# 0129-codec-mp3.net
KiCad netlist of a schematic drawn in EAGLE
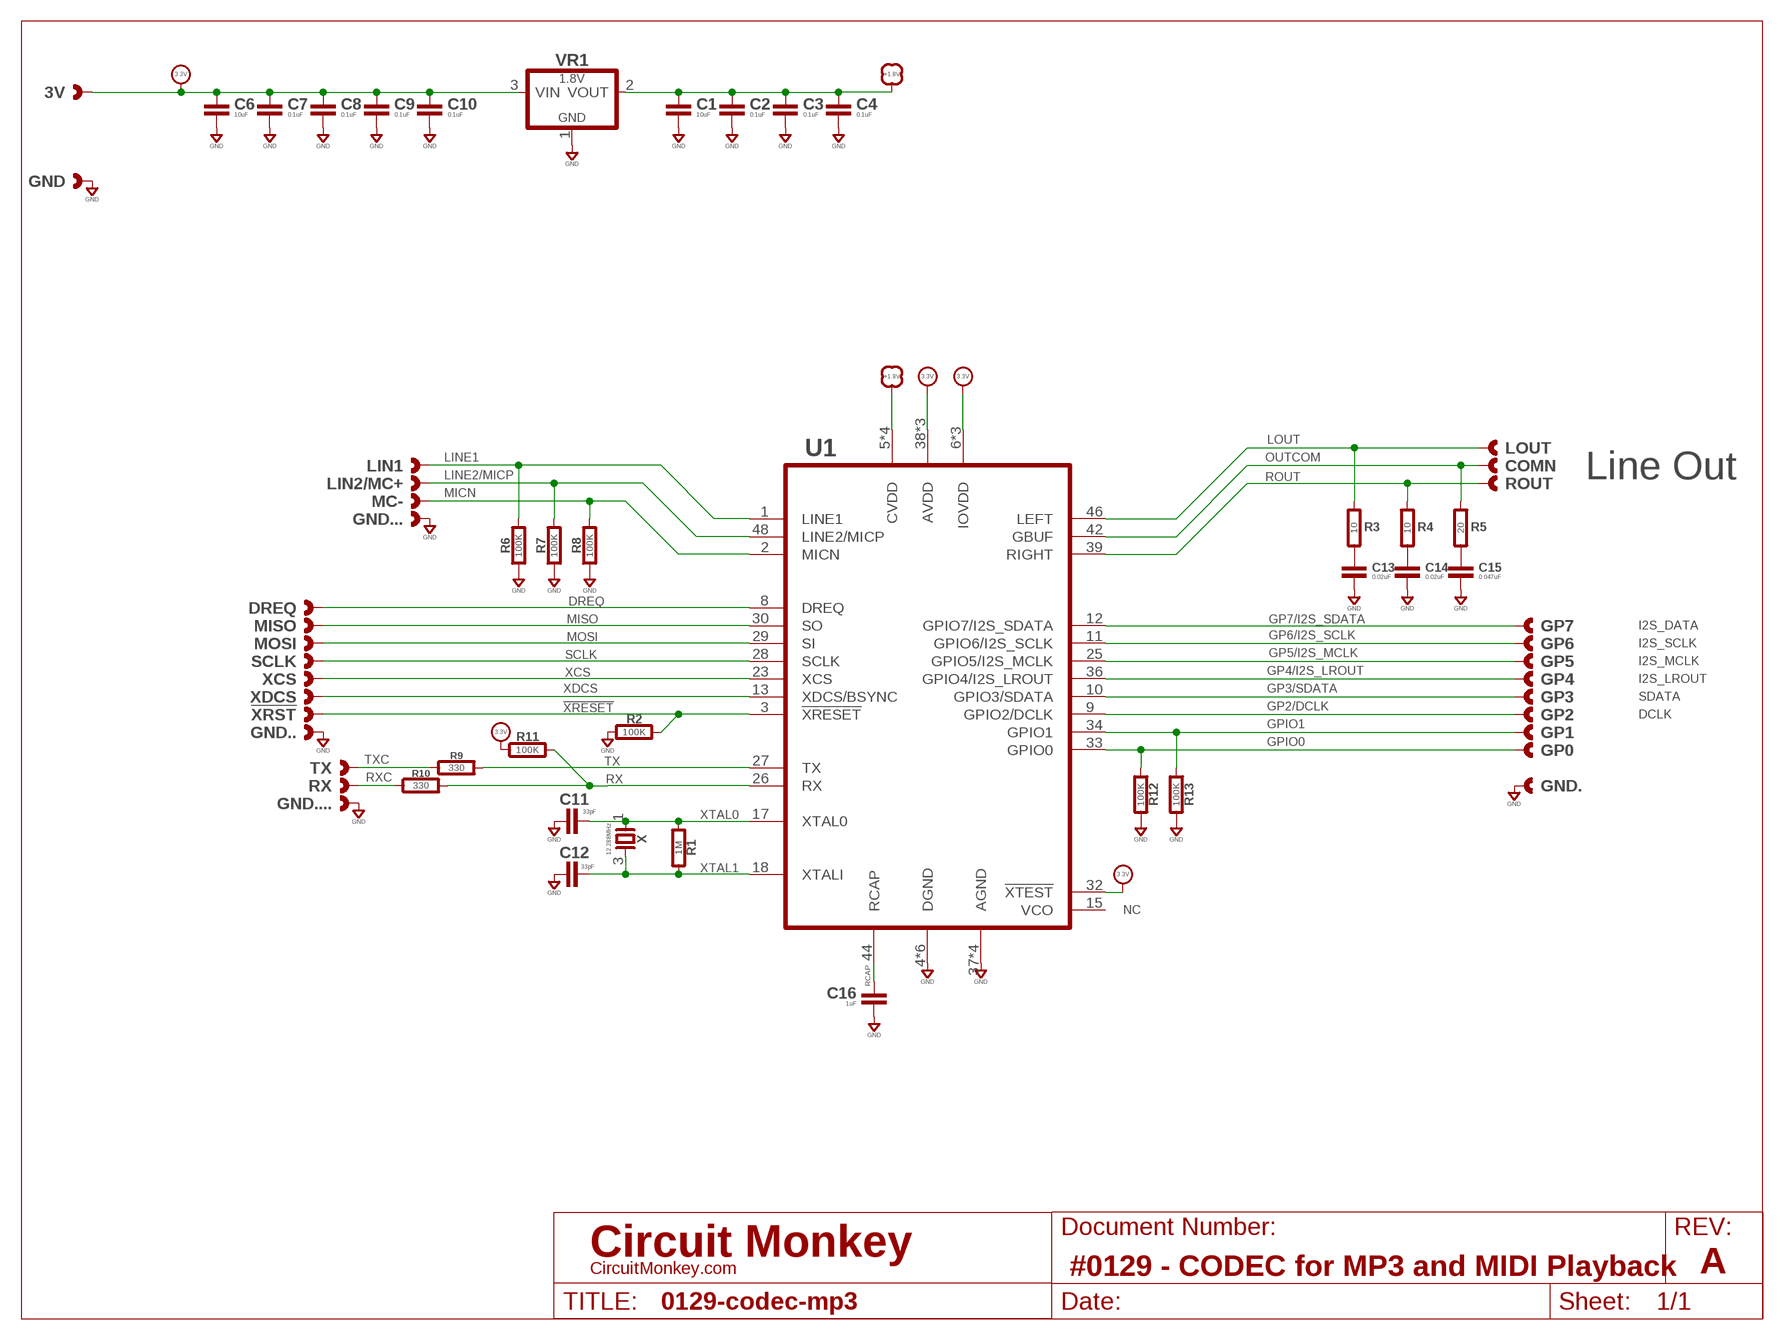
[diagram p0: schematic, sheet 1]

(export (version "E")
  (design (tool "Eeschema 10.0.6"))
  (components
    (comp (ref "!XRST")
      (value "CAST-01X12.00MM")
      (footprint "eagle-import:CAST01-2.00MM")
      (libsource (lib "eagle-import") (part "CAST-01X12.00MM"))
    )
    (comp (ref "3V")
      (value "CAST-01X12.00MM")
      (footprint "eagle-import:CAST01-2.00MM")
      (libsource (lib "eagle-import") (part "CAST-01X12.00MM"))
    )
    (comp (ref "C1")
      (value "10uF")
      (footprint "eagle-import:0603-CAP")
      (libsource (lib "eagle-import") (part "CAPACITOR0603"))
    )
    (comp (ref "C2")
      (value "0.1uF")
      (footprint "eagle-import:0603-CAP")
      (libsource (lib "eagle-import") (part "CAPACITOR0603"))
    )
    (comp (ref "C3")
      (value "0.1uF")
      (footprint "eagle-import:0603-CAP")
      (libsource (lib "eagle-import") (part "CAPACITOR0603"))
    )
    (comp (ref "C4")
      (value "0.1uF")
      (footprint "eagle-import:0603-CAP")
      (libsource (lib "eagle-import") (part "CAPACITOR0603"))
    )
    (comp (ref "C6")
      (value "10uF")
      (footprint "eagle-import:0603-CAP")
      (libsource (lib "eagle-import") (part "CAPACITOR0603"))
    )
    (comp (ref "C7")
      (value "0.1uF")
      (footprint "eagle-import:0603-CAP")
      (libsource (lib "eagle-import") (part "CAPACITOR0603"))
    )
    (comp (ref "C8")
      (value "0.1uF")
      (footprint "eagle-import:0603-CAP")
      (libsource (lib "eagle-import") (part "CAPACITOR0603"))
    )
    (comp (ref "C9")
      (value "0.1uF")
      (footprint "eagle-import:0603-CAP")
      (libsource (lib "eagle-import") (part "CAPACITOR0603"))
    )
    (comp (ref "C10")
      (value "0.1uF")
      (footprint "eagle-import:0603-CAP")
      (libsource (lib "eagle-import") (part "CAPACITOR0603"))
    )
    (comp (ref "C11")
      (value "33pF")
      (footprint "eagle-import:0603-CAP")
      (libsource (lib "eagle-import") (part "CAPACITOR0603"))
    )
    (comp (ref "C12")
      (value "33pF")
      (footprint "eagle-import:0603-CAP")
      (libsource (lib "eagle-import") (part "CAPACITOR0603"))
    )
    (comp (ref "C13")
      (value "0.02uF")
      (footprint "eagle-import:0603-CAP")
      (libsource (lib "eagle-import") (part "CAPACITOR0603"))
    )
    (comp (ref "C14")
      (value "0.02uF")
      (footprint "eagle-import:0603-CAP")
      (libsource (lib "eagle-import") (part "CAPACITOR0603"))
    )
    (comp (ref "C15")
      (value "0.047uF")
      (footprint "eagle-import:0603-CAP")
      (libsource (lib "eagle-import") (part "CAPACITOR0603"))
    )
    (comp (ref "C16")
      (value "1uF")
      (footprint "eagle-import:0603-CAP")
      (libsource (lib "eagle-import") (part "CAPACITOR0603"))
    )
    (comp (ref "COMN")
      (value "CAST-01X12.00MM")
      (footprint "eagle-import:CAST01-2.00MM")
      (libsource (lib "eagle-import") (part "CAST-01X12.00MM"))
    )
    (comp (ref "DREQ")
      (value "CAST-01X12.00MM")
      (footprint "eagle-import:CAST01-2.00MM")
      (libsource (lib "eagle-import") (part "CAST-01X12.00MM"))
    )
    (comp (ref "GND")
      (value "CAST-01X12.00MM")
      (footprint "eagle-import:CAST01-2.00MM")
      (libsource (lib "eagle-import") (part "CAST-01X12.00MM"))
    )
    (comp (ref "GND.")
      (value "CAST-01X12.00MM")
      (footprint "eagle-import:CAST01-2.00MM")
      (libsource (lib "eagle-import") (part "CAST-01X12.00MM"))
    )
    (comp (ref "GND..")
      (value "CAST-01X12.00MM")
      (footprint "eagle-import:CAST01-2.00MM")
      (libsource (lib "eagle-import") (part "CAST-01X12.00MM"))
    )
    (comp (ref "GND...")
      (value "CAST-01X12.00MM")
      (footprint "eagle-import:CAST01-2.00MM")
      (libsource (lib "eagle-import") (part "CAST-01X12.00MM"))
    )
    (comp (ref "GND....")
      (value "CAST-01X12.00MM")
      (footprint "eagle-import:CAST01-2.00MM")
      (libsource (lib "eagle-import") (part "CAST-01X12.00MM"))
    )
    (comp (ref "GP0")
      (value "CAST-01X12.00MM")
      (footprint "eagle-import:CAST01-2.00MM")
      (libsource (lib "eagle-import") (part "CAST-01X12.00MM"))
    )
    (comp (ref "GP1")
      (value "CAST-01X12.00MM")
      (footprint "eagle-import:CAST01-2.00MM")
      (libsource (lib "eagle-import") (part "CAST-01X12.00MM"))
    )
    (comp (ref "GP2")
      (value "CAST-01X12.00MM")
      (footprint "eagle-import:CAST01-2.00MM")
      (libsource (lib "eagle-import") (part "CAST-01X12.00MM"))
    )
    (comp (ref "GP3")
      (value "CAST-01X12.00MM")
      (footprint "eagle-import:CAST01-2.00MM")
      (libsource (lib "eagle-import") (part "CAST-01X12.00MM"))
    )
    (comp (ref "GP4")
      (value "CAST-01X12.00MM")
      (footprint "eagle-import:CAST01-2.00MM")
      (libsource (lib "eagle-import") (part "CAST-01X12.00MM"))
    )
    (comp (ref "GP5")
      (value "CAST-01X12.00MM")
      (footprint "eagle-import:CAST01-2.00MM")
      (libsource (lib "eagle-import") (part "CAST-01X12.00MM"))
    )
    (comp (ref "GP6")
      (value "CAST-01X12.00MM")
      (footprint "eagle-import:CAST01-2.00MM")
      (libsource (lib "eagle-import") (part "CAST-01X12.00MM"))
    )
    (comp (ref "GP7")
      (value "CAST-01X12.00MM")
      (footprint "eagle-import:CAST01-2.00MM")
      (libsource (lib "eagle-import") (part "CAST-01X12.00MM"))
    )
    (comp (ref "LIN1")
      (value "CAST-01X12.00MM")
      (footprint "eagle-import:CAST01-2.00MM")
      (libsource (lib "eagle-import") (part "CAST-01X12.00MM"))
    )
    (comp (ref "LIN2/MC+")
      (value "CAST-01X12.00MM")
      (footprint "eagle-import:CAST01-2.00MM")
      (libsource (lib "eagle-import") (part "CAST-01X12.00MM"))
    )
    (comp (ref "LOUT")
      (value "CAST-01X12.00MM")
      (footprint "eagle-import:CAST01-2.00MM")
      (libsource (lib "eagle-import") (part "CAST-01X12.00MM"))
    )
    (comp (ref "MC-")
      (value "CAST-01X12.00MM")
      (footprint "eagle-import:CAST01-2.00MM")
      (libsource (lib "eagle-import") (part "CAST-01X12.00MM"))
    )
    (comp (ref "MISO")
      (value "CAST-01X12.00MM")
      (footprint "eagle-import:CAST01-2.00MM")
      (libsource (lib "eagle-import") (part "CAST-01X12.00MM"))
    )
    (comp (ref "MOSI")
      (value "CAST-01X12.00MM")
      (footprint "eagle-import:CAST01-2.00MM")
      (libsource (lib "eagle-import") (part "CAST-01X12.00MM"))
    )
    (comp (ref "R1")
      (value "1M")
      (footprint "eagle-import:0603-RES")
      (libsource (lib "eagle-import") (part "RESISTOR0603"))
    )
    (comp (ref "R2")
      (value "100K")
      (footprint "eagle-import:0603-RES")
      (libsource (lib "eagle-import") (part "RESISTOR0603"))
    )
    (comp (ref "R3")
      (value "10")
      (footprint "eagle-import:0603-RES")
      (libsource (lib "eagle-import") (part "RESISTOR0603"))
    )
    (comp (ref "R4")
      (value "10")
      (footprint "eagle-import:0603-RES")
      (libsource (lib "eagle-import") (part "RESISTOR0603"))
    )
    (comp (ref "R5")
      (value "20")
      (footprint "eagle-import:0603-RES")
      (libsource (lib "eagle-import") (part "RESISTOR0603"))
    )
    (comp (ref "R6")
      (value "100K")
      (footprint "eagle-import:0603-RES")
      (libsource (lib "eagle-import") (part "RESISTOR0603"))
    )
    (comp (ref "R7")
      (value "100K")
      (footprint "eagle-import:0603-RES")
      (libsource (lib "eagle-import") (part "RESISTOR0603"))
    )
    (comp (ref "R8")
      (value "100K")
      (footprint "eagle-import:0603-RES")
      (libsource (lib "eagle-import") (part "RESISTOR0603"))
    )
    (comp (ref "R9")
      (value "330")
      (footprint "eagle-import:0603-RES")
      (libsource (lib "eagle-import") (part "RESISTOR0603"))
    )
    (comp (ref "R10")
      (value "330")
      (footprint "eagle-import:0603-RES")
      (libsource (lib "eagle-import") (part "RESISTOR0603"))
    )
    (comp (ref "R11")
      (value "100K")
      (footprint "eagle-import:0603-RES")
      (libsource (lib "eagle-import") (part "RESISTOR0603"))
    )
    (comp (ref "R12")
      (value "100K")
      (footprint "eagle-import:0603-RES")
      (libsource (lib "eagle-import") (part "RESISTOR0603"))
    )
    (comp (ref "R13")
      (value "100K")
      (footprint "eagle-import:0603-RES")
      (libsource (lib "eagle-import") (part "RESISTOR0603"))
    )
    (comp (ref "ROUT")
      (value "CAST-01X12.00MM")
      (footprint "eagle-import:CAST01-2.00MM")
      (libsource (lib "eagle-import") (part "CAST-01X12.00MM"))
    )
    (comp (ref "RX")
      (value "CAST-01X12.00MM")
      (footprint "eagle-import:CAST01-2.00MM")
      (libsource (lib "eagle-import") (part "CAST-01X12.00MM"))
    )
    (comp (ref "SCLK")
      (value "CAST-01X12.00MM")
      (footprint "eagle-import:CAST01-2.00MM")
      (libsource (lib "eagle-import") (part "CAST-01X12.00MM"))
    )
    (comp (ref "TX")
      (value "CAST-01X12.00MM")
      (footprint "eagle-import:CAST01-2.00MM")
      (libsource (lib "eagle-import") (part "CAST-01X12.00MM"))
    )
    (comp (ref "U1")
      (value "CODEC-VS1053")
      (footprint "eagle-import:LQFP-48")
      (libsource (lib "eagle-import") (part "CODEC-VS1053"))
    )
    (comp (ref "VR1")
      (value "1.8V")
      (footprint "eagle-import:SOT-23")
      (fields (field (name "MFR") "Diodes, Inc.") (field (name "MPN") "AP2120N-1.8"))
      (libsource (lib "eagle-import") (part "LDO-3P--1.8V-SOT23"))
    )
    (comp (ref "X")
      (value "12.288MHz")
      (footprint "eagle-import:32X25")
      (fields (field (name "MPN") "ABM8G-12.2-18D2Y"))
      (libsource (lib "eagle-import") (part "2P32X25-12.288MHZ"))
    )
    (comp (ref "XCS")
      (value "CAST-01X12.00MM")
      (footprint "eagle-import:CAST01-2.00MM")
      (libsource (lib "eagle-import") (part "CAST-01X12.00MM"))
    )
    (comp (ref "XDCS")
      (value "CAST-01X12.00MM")
      (footprint "eagle-import:CAST01-2.00MM")
      (libsource (lib "eagle-import") (part "CAST-01X12.00MM"))
    )
  )
  (nets
    (net (code "1") (name "+1.8V") (class "Default")
      (node (ref "C1") (pin "1") (pinfunction "1_1") (pintype "passive"))
      (node (ref "C2") (pin "1") (pinfunction "1_1") (pintype "passive"))
      (node (ref "C3") (pin "1") (pinfunction "1_1") (pintype "passive"))
      (node (ref "C4") (pin "1") (pinfunction "1_1") (pintype "passive"))
      (node (ref "U1") (pin "24") (pinfunction "CVDD_24") (pintype "power_in"))
      (node (ref "U1") (pin "31") (pinfunction "CVDD_31") (pintype "power_in"))
      (node (ref "U1") (pin "5") (pinfunction "CVDD_5") (pintype "power_in"))
      (node (ref "U1") (pin "7") (pinfunction "CVDD_7") (pintype "power_in"))
      (node (ref "VR1") (pin "2") (pinfunction "VOUT_2") (pintype "power_in"))
    )
    (net (code "2") (name "/DREQ") (class "Default")
      (node (ref "DREQ") (pin "1") (pinfunction "1_1") (pintype "bidirectional"))
      (node (ref "DREQ") (pin "P$1") (pinfunction "1_P$1") (pintype "bidirectional"))
      (node (ref "DREQ") (pin "P$2") (pinfunction "1_P$2") (pintype "bidirectional"))
      (node (ref "U1") (pin "8") (pinfunction "DREQ_8") (pintype "output"))
    )
    (net (code "3") (name "/GP2{slash}DCLK") (class "Default")
      (node (ref "GP2") (pin "1") (pinfunction "1_1") (pintype "bidirectional"))
      (node (ref "GP2") (pin "P$1") (pinfunction "1_P$1") (pintype "bidirectional"))
      (node (ref "GP2") (pin "P$2") (pinfunction "1_P$2") (pintype "bidirectional"))
      (node (ref "U1") (pin "9") (pinfunction "GPIO2/DCLK_9") (pintype "bidirectional"))
    )
    (net (code "4") (name "/GP3{slash}SDATA") (class "Default")
      (node (ref "GP3") (pin "1") (pinfunction "1_1") (pintype "bidirectional"))
      (node (ref "GP3") (pin "P$1") (pinfunction "1_P$1") (pintype "bidirectional"))
      (node (ref "GP3") (pin "P$2") (pinfunction "1_P$2") (pintype "bidirectional"))
      (node (ref "U1") (pin "10") (pinfunction "GPIO3/SDATA_10") (pintype "bidirectional"))
    )
    (net (code "5") (name "/GP4{slash}I2S_LROUT") (class "Default")
      (node (ref "GP4") (pin "1") (pinfunction "1_1") (pintype "bidirectional"))
      (node (ref "GP4") (pin "P$1") (pinfunction "1_P$1") (pintype "bidirectional"))
      (node (ref "GP4") (pin "P$2") (pinfunction "1_P$2") (pintype "bidirectional"))
      (node (ref "U1") (pin "36") (pinfunction "GPIO4/I2S_LROUT_36") (pintype "output"))
    )
    (net (code "6") (name "/GP5{slash}I2S_MCLK") (class "Default")
      (node (ref "GP5") (pin "1") (pinfunction "1_1") (pintype "bidirectional"))
      (node (ref "GP5") (pin "P$1") (pinfunction "1_P$1") (pintype "bidirectional"))
      (node (ref "GP5") (pin "P$2") (pinfunction "1_P$2") (pintype "bidirectional"))
      (node (ref "U1") (pin "25") (pinfunction "GPIO5/I2S_MCLK_25") (pintype "output"))
    )
    (net (code "7") (name "/GP6{slash}I2S_SCLK") (class "Default")
      (node (ref "GP6") (pin "1") (pinfunction "1_1") (pintype "bidirectional"))
      (node (ref "GP6") (pin "P$1") (pinfunction "1_P$1") (pintype "bidirectional"))
      (node (ref "GP6") (pin "P$2") (pinfunction "1_P$2") (pintype "bidirectional"))
      (node (ref "U1") (pin "11") (pinfunction "GPIO6/I2S_SCLK_11") (pintype "output"))
    )
    (net (code "8") (name "/GP7{slash}I2S_SDATA") (class "Default")
      (node (ref "GP7") (pin "1") (pinfunction "1_1") (pintype "bidirectional"))
      (node (ref "GP7") (pin "P$1") (pinfunction "1_P$1") (pintype "bidirectional"))
      (node (ref "GP7") (pin "P$2") (pinfunction "1_P$2") (pintype "bidirectional"))
      (node (ref "U1") (pin "12") (pinfunction "GPIO7/I2S_SDATA_12") (pintype "output"))
    )
    (net (code "9") (name "/GPIO0") (class "Default")
      (node (ref "GP0") (pin "1") (pinfunction "1_1") (pintype "bidirectional"))
      (node (ref "GP0") (pin "P$1") (pinfunction "1_P$1") (pintype "bidirectional"))
      (node (ref "GP0") (pin "P$2") (pinfunction "1_P$2") (pintype "bidirectional"))
      (node (ref "R12") (pin "1") (pinfunction "1_1") (pintype "passive"))
      (node (ref "U1") (pin "33") (pinfunction "GPIO0_33") (pintype "bidirectional"))
    )
    (net (code "10") (name "/GPIO1") (class "Default")
      (node (ref "GP1") (pin "1") (pinfunction "1_1") (pintype "bidirectional"))
      (node (ref "GP1") (pin "P$1") (pinfunction "1_P$1") (pintype "bidirectional"))
      (node (ref "GP1") (pin "P$2") (pinfunction "1_P$2") (pintype "bidirectional"))
      (node (ref "R13") (pin "1") (pinfunction "1_1") (pintype "passive"))
      (node (ref "U1") (pin "34") (pinfunction "GPIO1_34") (pintype "bidirectional"))
    )
    (net (code "11") (name "/LINE1") (class "Default")
      (node (ref "LIN1") (pin "1") (pinfunction "1_1") (pintype "bidirectional"))
      (node (ref "LIN1") (pin "P$1") (pinfunction "1_P$1") (pintype "bidirectional"))
      (node (ref "LIN1") (pin "P$2") (pinfunction "1_P$2") (pintype "bidirectional"))
      (node (ref "R6") (pin "2") (pinfunction "2_2") (pintype "passive"))
      (node (ref "U1") (pin "1") (pinfunction "LINE1_1") (pintype "input"))
    )
    (net (code "12") (name "/LINE2{slash}MICP") (class "Default")
      (node (ref "LIN2/MC+") (pin "1") (pinfunction "1_1") (pintype "bidirectional"))
      (node (ref "LIN2/MC+") (pin "P$1") (pinfunction "1_P$1") (pintype "bidirectional"))
      (node (ref "LIN2/MC+") (pin "P$2") (pinfunction "1_P$2") (pintype "bidirectional"))
      (node (ref "R7") (pin "2") (pinfunction "2_2") (pintype "passive"))
      (node (ref "U1") (pin "48") (pinfunction "LINE2/MICP_48") (pintype "input"))
    )
    (net (code "13") (name "/LOUT") (class "Default")
      (node (ref "LOUT") (pin "1") (pinfunction "1_1") (pintype "bidirectional"))
      (node (ref "LOUT") (pin "P$1") (pinfunction "1_P$1") (pintype "bidirectional"))
      (node (ref "LOUT") (pin "P$2") (pinfunction "1_P$2") (pintype "bidirectional"))
      (node (ref "R3") (pin "1") (pinfunction "1_1") (pintype "passive"))
      (node (ref "U1") (pin "46") (pinfunction "LEFT_46") (pintype "output"))
    )
    (net (code "14") (name "/MICN") (class "Default")
      (node (ref "MC-") (pin "1") (pinfunction "1_1") (pintype "bidirectional"))
      (node (ref "MC-") (pin "P$1") (pinfunction "1_P$1") (pintype "bidirectional"))
      (node (ref "MC-") (pin "P$2") (pinfunction "1_P$2") (pintype "bidirectional"))
      (node (ref "R8") (pin "2") (pinfunction "2_2") (pintype "passive"))
      (node (ref "U1") (pin "2") (pinfunction "MICN_2") (pintype "input"))
    )
    (net (code "15") (name "/MISO") (class "Default")
      (node (ref "MISO") (pin "1") (pinfunction "1_1") (pintype "bidirectional"))
      (node (ref "MISO") (pin "P$1") (pinfunction "1_P$1") (pintype "bidirectional"))
      (node (ref "MISO") (pin "P$2") (pinfunction "1_P$2") (pintype "bidirectional"))
      (node (ref "U1") (pin "30") (pinfunction "SO_30") (pintype "output"))
    )
    (net (code "16") (name "/MOSI") (class "Default")
      (node (ref "MOSI") (pin "1") (pinfunction "1_1") (pintype "bidirectional"))
      (node (ref "MOSI") (pin "P$1") (pinfunction "1_P$1") (pintype "bidirectional"))
      (node (ref "MOSI") (pin "P$2") (pinfunction "1_P$2") (pintype "bidirectional"))
      (node (ref "U1") (pin "29") (pinfunction "SI_29") (pintype "input"))
    )
    (net (code "17") (name "/OUTCOM") (class "Default")
      (node (ref "COMN") (pin "1") (pinfunction "1_1") (pintype "bidirectional"))
      (node (ref "COMN") (pin "P$1") (pinfunction "1_P$1") (pintype "bidirectional"))
      (node (ref "COMN") (pin "P$2") (pinfunction "1_P$2") (pintype "bidirectional"))
      (node (ref "R5") (pin "1") (pinfunction "1_1") (pintype "passive"))
      (node (ref "U1") (pin "42") (pinfunction "GBUF_42") (pintype "output"))
    )
    (net (code "18") (name "/RCAP") (class "Default")
      (node (ref "C16") (pin "1") (pinfunction "1_1") (pintype "passive"))
      (node (ref "U1") (pin "44") (pinfunction "RCAP_44") (pintype "passive"))
    )
    (net (code "19") (name "/ROUT") (class "Default")
      (node (ref "R4") (pin "1") (pinfunction "1_1") (pintype "passive"))
      (node (ref "ROUT") (pin "1") (pinfunction "1_1") (pintype "bidirectional"))
      (node (ref "ROUT") (pin "P$1") (pinfunction "1_P$1") (pintype "bidirectional"))
      (node (ref "ROUT") (pin "P$2") (pinfunction "1_P$2") (pintype "bidirectional"))
      (node (ref "U1") (pin "39") (pinfunction "RIGHT_39") (pintype "output"))
    )
    (net (code "20") (name "/RX") (class "Default")
      (node (ref "R10") (pin "2") (pinfunction "2_2") (pintype "passive"))
      (node (ref "R11") (pin "2") (pinfunction "2_2") (pintype "passive"))
      (node (ref "U1") (pin "26") (pinfunction "RX_26") (pintype "input"))
    )
    (net (code "21") (name "/RXC") (class "Default")
      (node (ref "R10") (pin "1") (pinfunction "1_1") (pintype "passive"))
      (node (ref "RX") (pin "1") (pinfunction "1_1") (pintype "bidirectional"))
      (node (ref "RX") (pin "P$1") (pinfunction "1_P$1") (pintype "bidirectional"))
      (node (ref "RX") (pin "P$2") (pinfunction "1_P$2") (pintype "bidirectional"))
    )
    (net (code "22") (name "/SCLK") (class "Default")
      (node (ref "SCLK") (pin "1") (pinfunction "1_1") (pintype "bidirectional"))
      (node (ref "SCLK") (pin "P$1") (pinfunction "1_P$1") (pintype "bidirectional"))
      (node (ref "SCLK") (pin "P$2") (pinfunction "1_P$2") (pintype "bidirectional"))
      (node (ref "U1") (pin "28") (pinfunction "SCLK_28") (pintype "input"))
    )
    (net (code "23") (name "/TX") (class "Default")
      (node (ref "R9") (pin "2") (pinfunction "2_2") (pintype "passive"))
      (node (ref "U1") (pin "27") (pinfunction "TX_27") (pintype "output"))
    )
    (net (code "24") (name "/TXC") (class "Default")
      (node (ref "R9") (pin "1") (pinfunction "1_1") (pintype "passive"))
      (node (ref "TX") (pin "1") (pinfunction "1_1") (pintype "bidirectional"))
      (node (ref "TX") (pin "P$1") (pinfunction "1_P$1") (pintype "bidirectional"))
      (node (ref "TX") (pin "P$2") (pinfunction "1_P$2") (pintype "bidirectional"))
    )
    (net (code "25") (name "/XCS") (class "Default")
      (node (ref "U1") (pin "23") (pinfunction "XCS_23") (pintype "input"))
      (node (ref "XCS") (pin "1") (pinfunction "1_1") (pintype "bidirectional"))
      (node (ref "XCS") (pin "P$1") (pinfunction "1_P$1") (pintype "bidirectional"))
      (node (ref "XCS") (pin "P$2") (pinfunction "1_P$2") (pintype "bidirectional"))
    )
    (net (code "26") (name "/XDCS") (class "Default")
      (node (ref "U1") (pin "13") (pinfunction "XDCS/BSYNC_13") (pintype "input"))
      (node (ref "XDCS") (pin "1") (pinfunction "1_1") (pintype "bidirectional"))
      (node (ref "XDCS") (pin "P$1") (pinfunction "1_P$1") (pintype "bidirectional"))
      (node (ref "XDCS") (pin "P$2") (pinfunction "1_P$2") (pintype "bidirectional"))
    )
    (net (code "27") (name "/XTAL0") (class "Default")
      (node (ref "C11") (pin "2") (pinfunction "2_2") (pintype "passive"))
      (node (ref "R1") (pin "1") (pinfunction "1_1") (pintype "passive"))
      (node (ref "U1") (pin "17") (pinfunction "XTAL0_17") (pintype "bidirectional"))
      (node (ref "X") (pin "1") (pinfunction "P$1_1") (pintype "passive"))
    )
    (net (code "28") (name "/XTAL1") (class "Default")
      (node (ref "C12") (pin "2") (pinfunction "2_2") (pintype "passive"))
      (node (ref "R1") (pin "2") (pinfunction "2_2") (pintype "passive"))
      (node (ref "U1") (pin "18") (pinfunction "XTALI_18") (pintype "bidirectional"))
      (node (ref "X") (pin "3") (pinfunction "P$2_3") (pintype "passive"))
    )
    (net (code "29") (name "/~{XRESET}") (class "Default")
      (node (ref "!XRST") (pin "1") (pinfunction "1_1") (pintype "bidirectional"))
      (node (ref "!XRST") (pin "P$1") (pinfunction "1_P$1") (pintype "bidirectional"))
      (node (ref "!XRST") (pin "P$2") (pinfunction "1_P$2") (pintype "bidirectional"))
      (node (ref "R2") (pin "2") (pinfunction "2_2") (pintype "passive"))
      (node (ref "U1") (pin "3") (pinfunction "~{XRESET}_3") (pintype "input"))
    )
    (net (code "30") (name "3.3V") (class "Default")
      (node (ref "3V") (pin "1") (pinfunction "1_1") (pintype "bidirectional"))
      (node (ref "3V") (pin "P$1") (pinfunction "1_P$1") (pintype "bidirectional"))
      (node (ref "3V") (pin "P$2") (pinfunction "1_P$2") (pintype "bidirectional"))
      (node (ref "C10") (pin "1") (pinfunction "1_1") (pintype "passive"))
      (node (ref "C6") (pin "1") (pinfunction "1_1") (pintype "passive"))
      (node (ref "C7") (pin "1") (pinfunction "1_1") (pintype "passive"))
      (node (ref "C8") (pin "1") (pinfunction "1_1") (pintype "passive"))
      (node (ref "C9") (pin "1") (pinfunction "1_1") (pintype "passive"))
      (node (ref "R11") (pin "1") (pinfunction "1_1") (pintype "passive"))
      (node (ref "U1") (pin "14") (pinfunction "IOVDD_14") (pintype "power_in"))
      (node (ref "U1") (pin "19") (pinfunction "IOVDD_19") (pintype "power_in"))
      (node (ref "U1") (pin "32") (pinfunction "~{XTEST}_32") (pintype "input"))
      (node (ref "U1") (pin "38") (pinfunction "AVDD_38") (pintype "power_in"))
      (node (ref "U1") (pin "43") (pinfunction "AVDD_43") (pintype "power_in"))
      (node (ref "U1") (pin "45") (pinfunction "AVDD_45") (pintype "power_in"))
      (node (ref "U1") (pin "6") (pinfunction "IOVDD_6") (pintype "power_in"))
      (node (ref "VR1") (pin "3") (pinfunction "VIN_3") (pintype "power_in"))
    )
    (net (code "31") (name "GND") (class "Default")
      (node (ref "C1") (pin "2") (pinfunction "2_2") (pintype "passive"))
      (node (ref "C10") (pin "2") (pinfunction "2_2") (pintype "passive"))
      (node (ref "C11") (pin "1") (pinfunction "1_1") (pintype "passive"))
      (node (ref "C12") (pin "1") (pinfunction "1_1") (pintype "passive"))
      (node (ref "C13") (pin "2") (pinfunction "2_2") (pintype "passive"))
      (node (ref "C14") (pin "2") (pinfunction "2_2") (pintype "passive"))
      (node (ref "C15") (pin "2") (pinfunction "2_2") (pintype "passive"))
      (node (ref "C16") (pin "2") (pinfunction "2_2") (pintype "passive"))
      (node (ref "C2") (pin "2") (pinfunction "2_2") (pintype "passive"))
      (node (ref "C3") (pin "2") (pinfunction "2_2") (pintype "passive"))
      (node (ref "C4") (pin "2") (pinfunction "2_2") (pintype "passive"))
      (node (ref "C6") (pin "2") (pinfunction "2_2") (pintype "passive"))
      (node (ref "C7") (pin "2") (pinfunction "2_2") (pintype "passive"))
      (node (ref "C8") (pin "2") (pinfunction "2_2") (pintype "passive"))
      (node (ref "C9") (pin "2") (pinfunction "2_2") (pintype "passive"))
      (node (ref "GND") (pin "1") (pinfunction "1_1") (pintype "bidirectional"))
      (node (ref "GND") (pin "P$1") (pinfunction "1_P$1") (pintype "bidirectional"))
      (node (ref "GND") (pin "P$2") (pinfunction "1_P$2") (pintype "bidirectional"))
      (node (ref "GND.") (pin "1") (pinfunction "1_1") (pintype "bidirectional"))
      (node (ref "GND.") (pin "P$1") (pinfunction "1_P$1") (pintype "bidirectional"))
      (node (ref "GND.") (pin "P$2") (pinfunction "1_P$2") (pintype "bidirectional"))
      (node (ref "GND..") (pin "1") (pinfunction "1_1") (pintype "bidirectional"))
      (node (ref "GND..") (pin "P$1") (pinfunction "1_P$1") (pintype "bidirectional"))
      (node (ref "GND..") (pin "P$2") (pinfunction "1_P$2") (pintype "bidirectional"))
      (node (ref "GND...") (pin "1") (pinfunction "1_1") (pintype "bidirectional"))
      (node (ref "GND...") (pin "P$1") (pinfunction "1_P$1") (pintype "bidirectional"))
      (node (ref "GND...") (pin "P$2") (pinfunction "1_P$2") (pintype "bidirectional"))
      (node (ref "GND....") (pin "1") (pinfunction "1_1") (pintype "bidirectional"))
      (node (ref "GND....") (pin "P$1") (pinfunction "1_P$1") (pintype "bidirectional"))
      (node (ref "GND....") (pin "P$2") (pinfunction "1_P$2") (pintype "bidirectional"))
      (node (ref "R12") (pin "2") (pinfunction "2_2") (pintype "passive"))
      (node (ref "R13") (pin "2") (pinfunction "2_2") (pintype "passive"))
      (node (ref "R2") (pin "1") (pinfunction "1_1") (pintype "passive"))
      (node (ref "R6") (pin "1") (pinfunction "1_1") (pintype "passive"))
      (node (ref "R7") (pin "1") (pinfunction "1_1") (pintype "passive"))
      (node (ref "R8") (pin "1") (pinfunction "1_1") (pintype "passive"))
      (node (ref "U1") (pin "16") (pinfunction "DGND_16") (pintype "power_in"))
      (node (ref "U1") (pin "20") (pinfunction "DGND_20") (pintype "power_in"))
      (node (ref "U1") (pin "21") (pinfunction "DGND_21") (pintype "power_in"))
      (node (ref "U1") (pin "22") (pinfunction "DGND_22") (pintype "power_in"))
      (node (ref "U1") (pin "35") (pinfunction "DGND_35") (pintype "power_in"))
      (node (ref "U1") (pin "37") (pinfunction "AGND_37") (pintype "power_in"))
      (node (ref "U1") (pin "4") (pinfunction "DGND_4") (pintype "power_in"))
      (node (ref "U1") (pin "40") (pinfunction "AGND_40") (pintype "power_in"))
      (node (ref "U1") (pin "41") (pinfunction "AGND_41") (pintype "power_in"))
      (node (ref "U1") (pin "47") (pinfunction "AGND_47") (pintype "power_in"))
      (node (ref "VR1") (pin "1") (pinfunction "GND_1") (pintype "power_in"))
    )
    (net (code "32") (name "Net-(C13-Pad1)") (class "Default")
      (node (ref "C13") (pin "1") (pinfunction "1_1") (pintype "passive"))
      (node (ref "R3") (pin "2") (pinfunction "2_2") (pintype "passive"))
    )
    (net (code "33") (name "Net-(C14-Pad1)") (class "Default")
      (node (ref "C14") (pin "1") (pinfunction "1_1") (pintype "passive"))
      (node (ref "R4") (pin "2") (pinfunction "2_2") (pintype "passive"))
    )
    (net (code "34") (name "Net-(C15-Pad1)") (class "Default")
      (node (ref "C15") (pin "1") (pinfunction "1_1") (pintype "passive"))
      (node (ref "R5") (pin "2") (pinfunction "2_2") (pintype "passive"))
    )
    (net (code "35") (name "unconnected-(U1-VCO-Pad15)") (class "Default")
      (node (ref "U1") (pin "15") (pinfunction "VCO_15") (pintype "output"))
    )
  )
)
